# main_stack_dual_channel.net
KiCad netlist of a schematic drawn in Altium Designer
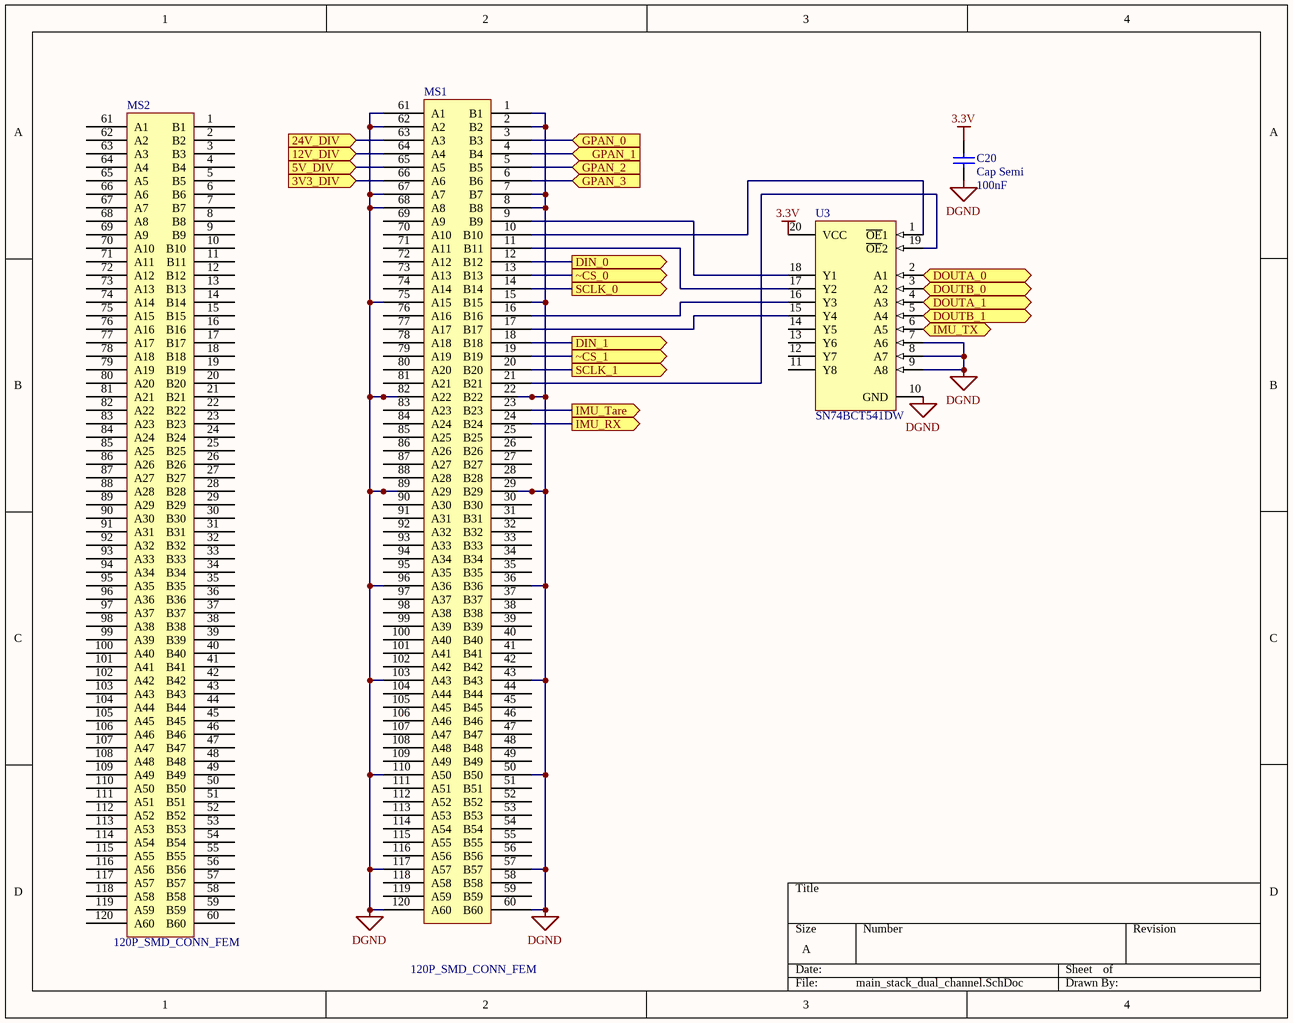
[diagram p0: main_stack_dual_channel.SchDoc]

(export (version "E")
  (design (tool "Eeschema 10.0.6"))
  (components
    (comp (ref "C20")
      (value "Cap Semi")
      (footprint "C0805")
      (description "Capacitor (Semiconductor SIM Model)")
      (fields (field (name "ALTIUM_VALUE") "100nF") (field (name "PUBLISHER") "Altium Limited"))
      (libsource (lib "Miscellaneous Devices") (part "Cap Semi"))
    )
    (comp (ref "MS1")
      (value "120P_SMD_CONN_FEM")
      (description "Main Stack Connector, Female")
      (fields (field (name "PART NUMBER") "FX2-120P-1.27SV(71)"))
      (libsource (lib "MDA_altium_common") (part "120P_SMD_CONN_FEM"))
    )
    (comp (ref "MS2")
      (value "120P_SMD_CONN_FEM")
      (description "Main Stack Connector, Female")
      (fields (field (name "PART NUMBER") "FX2-120P-1.27SV(71)"))
      (libsource (lib "MDA_altium_common") (part "120P_SMD_CONN_FEM"))
    )
    (comp (ref "U3")
      (value "SN74BCT541DW")
      (footprint "DW020_N")
      (description "Octal Buffer/Driver with 3-State Outputs")
      (fields (field (name "PUBLISHER") "Altium Limited"))
      (libsource (lib "TI Logic Buffer Line Driver") (part "SN74BCT541DW"))
    )
  )
  (nets
    (net (code "1") (name "/3V3_DIV") (class "Default")
      (node (ref "MS1") (pin "66") (pinfunction "A6_66") (pintype "passive"))
    )
    (net (code "2") (name "/5V_DIV") (class "Default")
      (node (ref "MS1") (pin "65") (pinfunction "A5_65") (pintype "passive"))
    )
    (net (code "3") (name "/12V_DIV") (class "Default")
      (node (ref "MS1") (pin "64") (pinfunction "A4_64") (pintype "passive"))
    )
    (net (code "4") (name "/24V_DIV") (class "Default")
      (node (ref "MS1") (pin "63") (pinfunction "A3_63") (pintype "passive"))
    )
    (net (code "5") (name "/DIN_0") (class "Default")
      (node (ref "MS1") (pin "12") (pinfunction "B12_12") (pintype "passive"))
    )
    (net (code "6") (name "/DIN_1") (class "Default")
      (node (ref "MS1") (pin "18") (pinfunction "B18_18") (pintype "passive"))
    )
    (net (code "7") (name "/DOUTA_0") (class "Default")
      (node (ref "U3") (pin "2") (pinfunction "A1_2") (pintype "input"))
    )
    (net (code "8") (name "/DOUTA_1") (class "Default")
      (node (ref "U3") (pin "4") (pinfunction "A3_4") (pintype "input"))
    )
    (net (code "9") (name "/DOUTB_0") (class "Default")
      (node (ref "U3") (pin "3") (pinfunction "A2_3") (pintype "input"))
    )
    (net (code "10") (name "/DOUTB_1") (class "Default")
      (node (ref "U3") (pin "5") (pinfunction "A4_5") (pintype "input"))
    )
    (net (code "11") (name "/GPAN_0") (class "Default")
      (node (ref "MS1") (pin "3") (pinfunction "B3_3") (pintype "passive"))
    )
    (net (code "12") (name "/GPAN_1") (class "Default")
      (node (ref "MS1") (pin "4") (pinfunction "B4_4") (pintype "passive"))
    )
    (net (code "13") (name "/GPAN_2") (class "Default")
      (node (ref "MS1") (pin "5") (pinfunction "B5_5") (pintype "passive"))
    )
    (net (code "14") (name "/GPAN_3") (class "Default")
      (node (ref "MS1") (pin "6") (pinfunction "B6_6") (pintype "passive"))
    )
    (net (code "15") (name "/IMU_RX") (class "Default")
      (node (ref "MS1") (pin "24") (pinfunction "B24_24") (pintype "passive"))
    )
    (net (code "16") (name "/IMU_TX") (class "Default")
      (node (ref "U3") (pin "6") (pinfunction "A5_6") (pintype "input"))
    )
    (net (code "17") (name "/IMU_Tare") (class "Default")
      (node (ref "MS1") (pin "23") (pinfunction "B23_23") (pintype "passive"))
    )
    (net (code "18") (name "/SCLK_0") (class "Default")
      (node (ref "MS1") (pin "14") (pinfunction "B14_14") (pintype "passive"))
    )
    (net (code "19") (name "/SCLK_1") (class "Default")
      (node (ref "MS1") (pin "20") (pinfunction "B20_20") (pintype "passive"))
    )
    (net (code "20") (name "/~CS_0") (class "Default")
      (node (ref "MS1") (pin "13") (pinfunction "B13_13") (pintype "passive"))
    )
    (net (code "21") (name "/~CS_1") (class "Default")
      (node (ref "MS1") (pin "19") (pinfunction "B19_19") (pintype "passive"))
    )
    (net (code "22") (name "3.3V") (class "Default")
      (node (ref "C20") (pin "2") (pinfunction "2_2") (pintype "passive"))
      (node (ref "U3") (pin "20") (pinfunction "VCC_20") (pintype "power_in"))
    )
    (net (code "23") (name "DGND") (class "Default")
      (node (ref "C20") (pin "1") (pinfunction "1_1") (pintype "passive"))
      (node (ref "MS1") (pin "1") (pinfunction "B1_1") (pintype "passive"))
      (node (ref "MS1") (pin "103") (pinfunction "A43_103") (pintype "passive"))
      (node (ref "MS1") (pin "110") (pinfunction "A50_110") (pintype "passive"))
      (node (ref "MS1") (pin "117") (pinfunction "A57_117") (pintype "passive"))
      (node (ref "MS1") (pin "120") (pinfunction "A60_120") (pintype "passive"))
      (node (ref "MS1") (pin "15") (pinfunction "B15_15") (pintype "passive"))
      (node (ref "MS1") (pin "2") (pinfunction "B2_2") (pintype "passive"))
      (node (ref "MS1") (pin "22") (pinfunction "B22_22") (pintype "passive"))
      (node (ref "MS1") (pin "29") (pinfunction "B29_29") (pintype "passive"))
      (node (ref "MS1") (pin "36") (pinfunction "B36_36") (pintype "passive"))
      (node (ref "MS1") (pin "43") (pinfunction "B43_43") (pintype "passive"))
      (node (ref "MS1") (pin "50") (pinfunction "B50_50") (pintype "passive"))
      (node (ref "MS1") (pin "57") (pinfunction "B57_57") (pintype "passive"))
      (node (ref "MS1") (pin "60") (pinfunction "B60_60") (pintype "passive"))
      (node (ref "MS1") (pin "61") (pinfunction "A1_61") (pintype "passive"))
      (node (ref "MS1") (pin "62") (pinfunction "A2_62") (pintype "passive"))
      (node (ref "MS1") (pin "67") (pinfunction "A7_67") (pintype "passive"))
      (node (ref "MS1") (pin "68") (pinfunction "A8_68") (pintype "passive"))
      (node (ref "MS1") (pin "7") (pinfunction "B7_7") (pintype "passive"))
      (node (ref "MS1") (pin "75") (pinfunction "A15_75") (pintype "passive"))
      (node (ref "MS1") (pin "8") (pinfunction "B8_8") (pintype "passive"))
      (node (ref "MS1") (pin "82") (pinfunction "A22_82") (pintype "passive"))
      (node (ref "MS1") (pin "89") (pinfunction "A29_89") (pintype "passive"))
      (node (ref "MS1") (pin "96") (pinfunction "A36_96") (pintype "passive"))
      (node (ref "U3") (pin "10") (pinfunction "GND_10") (pintype "power_in"))
      (node (ref "U3") (pin "7") (pinfunction "A6_7") (pintype "input"))
      (node (ref "U3") (pin "8") (pinfunction "A7_8") (pintype "input"))
      (node (ref "U3") (pin "9") (pinfunction "A8_9") (pintype "input"))
    )
    (net (code "24") (name "Net-(MS1-B9)") (class "Default")
      (node (ref "MS1") (pin "9") (pinfunction "B9_9") (pintype "passive"))
      (node (ref "U3") (pin "18") (pinfunction "Y1_18") (pintype "tri_state"))
    )
    (net (code "25") (name "Net-(MS1-B10)") (class "Default")
      (node (ref "MS1") (pin "10") (pinfunction "B10_10") (pintype "passive"))
      (node (ref "U3") (pin "1") (pinfunction "~{OE}1_1") (pintype "input"))
    )
    (net (code "26") (name "Net-(MS1-B11)") (class "Default")
      (node (ref "MS1") (pin "11") (pinfunction "B11_11") (pintype "passive"))
      (node (ref "U3") (pin "17") (pinfunction "Y2_17") (pintype "tri_state"))
    )
    (net (code "27") (name "Net-(MS1-B16)") (class "Default")
      (node (ref "MS1") (pin "16") (pinfunction "B16_16") (pintype "passive"))
      (node (ref "U3") (pin "16") (pinfunction "Y3_16") (pintype "tri_state"))
    )
    (net (code "28") (name "Net-(MS1-B17)") (class "Default")
      (node (ref "MS1") (pin "17") (pinfunction "B17_17") (pintype "passive"))
      (node (ref "U3") (pin "15") (pinfunction "Y4_15") (pintype "tri_state"))
    )
    (net (code "29") (name "Net-(MS1-B21)") (class "Default")
      (node (ref "MS1") (pin "21") (pinfunction "B21_21") (pintype "passive"))
      (node (ref "U3") (pin "19") (pinfunction "~{OE}2_19") (pintype "input"))
    )
    (net (code "30") (name "unconnected-(MS1-A9-Pad69)") (class "Default")
      (node (ref "MS1") (pin "69") (pinfunction "A9_69") (pintype "passive"))
    )
    (net (code "31") (name "unconnected-(MS1-A10-Pad70)") (class "Default")
      (node (ref "MS1") (pin "70") (pinfunction "A10_70") (pintype "passive"))
    )
    (net (code "32") (name "unconnected-(MS1-A11-Pad71)") (class "Default")
      (node (ref "MS1") (pin "71") (pinfunction "A11_71") (pintype "passive"))
    )
    (net (code "33") (name "unconnected-(MS1-A12-Pad72)") (class "Default")
      (node (ref "MS1") (pin "72") (pinfunction "A12_72") (pintype "passive"))
    )
    (net (code "34") (name "unconnected-(MS1-A13-Pad73)") (class "Default")
      (node (ref "MS1") (pin "73") (pinfunction "A13_73") (pintype "passive"))
    )
    (net (code "35") (name "unconnected-(MS1-A14-Pad74)") (class "Default")
      (node (ref "MS1") (pin "74") (pinfunction "A14_74") (pintype "passive"))
    )
    (net (code "36") (name "unconnected-(MS1-A16-Pad76)") (class "Default")
      (node (ref "MS1") (pin "76") (pinfunction "A16_76") (pintype "passive"))
    )
    (net (code "37") (name "unconnected-(MS1-A17-Pad77)") (class "Default")
      (node (ref "MS1") (pin "77") (pinfunction "A17_77") (pintype "passive"))
    )
    (net (code "38") (name "unconnected-(MS1-A18-Pad78)") (class "Default")
      (node (ref "MS1") (pin "78") (pinfunction "A18_78") (pintype "passive"))
    )
    (net (code "39") (name "unconnected-(MS1-A19-Pad79)") (class "Default")
      (node (ref "MS1") (pin "79") (pinfunction "A19_79") (pintype "passive"))
    )
    (net (code "40") (name "unconnected-(MS1-A20-Pad80)") (class "Default")
      (node (ref "MS1") (pin "80") (pinfunction "A20_80") (pintype "passive"))
    )
    (net (code "41") (name "unconnected-(MS1-A21-Pad81)") (class "Default")
      (node (ref "MS1") (pin "81") (pinfunction "A21_81") (pintype "passive"))
    )
    (net (code "42") (name "unconnected-(MS1-A23-Pad83)") (class "Default")
      (node (ref "MS1") (pin "83") (pinfunction "A23_83") (pintype "passive"))
    )
    (net (code "43") (name "unconnected-(MS1-A24-Pad84)") (class "Default")
      (node (ref "MS1") (pin "84") (pinfunction "A24_84") (pintype "passive"))
    )
    (net (code "44") (name "unconnected-(MS1-A25-Pad85)") (class "Default")
      (node (ref "MS1") (pin "85") (pinfunction "A25_85") (pintype "passive"))
    )
    (net (code "45") (name "unconnected-(MS1-A26-Pad86)") (class "Default")
      (node (ref "MS1") (pin "86") (pinfunction "A26_86") (pintype "passive"))
    )
    (net (code "46") (name "unconnected-(MS1-A27-Pad87)") (class "Default")
      (node (ref "MS1") (pin "87") (pinfunction "A27_87") (pintype "passive"))
    )
    (net (code "47") (name "unconnected-(MS1-A28-Pad88)") (class "Default")
      (node (ref "MS1") (pin "88") (pinfunction "A28_88") (pintype "passive"))
    )
    (net (code "48") (name "unconnected-(MS1-A30-Pad90)") (class "Default")
      (node (ref "MS1") (pin "90") (pinfunction "A30_90") (pintype "passive"))
    )
    (net (code "49") (name "unconnected-(MS1-A31-Pad91)") (class "Default")
      (node (ref "MS1") (pin "91") (pinfunction "A31_91") (pintype "passive"))
    )
    (net (code "50") (name "unconnected-(MS1-A32-Pad92)") (class "Default")
      (node (ref "MS1") (pin "92") (pinfunction "A32_92") (pintype "passive"))
    )
    (net (code "51") (name "unconnected-(MS1-A33-Pad93)") (class "Default")
      (node (ref "MS1") (pin "93") (pinfunction "A33_93") (pintype "passive"))
    )
    (net (code "52") (name "unconnected-(MS1-A34-Pad94)") (class "Default")
      (node (ref "MS1") (pin "94") (pinfunction "A34_94") (pintype "passive"))
    )
    (net (code "53") (name "unconnected-(MS1-A35-Pad95)") (class "Default")
      (node (ref "MS1") (pin "95") (pinfunction "A35_95") (pintype "passive"))
    )
    (net (code "54") (name "unconnected-(MS1-A37-Pad97)") (class "Default")
      (node (ref "MS1") (pin "97") (pinfunction "A37_97") (pintype "passive"))
    )
    (net (code "55") (name "unconnected-(MS1-A38-Pad98)") (class "Default")
      (node (ref "MS1") (pin "98") (pinfunction "A38_98") (pintype "passive"))
    )
    (net (code "56") (name "unconnected-(MS1-A39-Pad99)") (class "Default")
      (node (ref "MS1") (pin "99") (pinfunction "A39_99") (pintype "passive"))
    )
    (net (code "57") (name "unconnected-(MS1-A40-Pad100)") (class "Default")
      (node (ref "MS1") (pin "100") (pinfunction "A40_100") (pintype "passive"))
    )
    (net (code "58") (name "unconnected-(MS1-A41-Pad101)") (class "Default")
      (node (ref "MS1") (pin "101") (pinfunction "A41_101") (pintype "passive"))
    )
    (net (code "59") (name "unconnected-(MS1-A42-Pad102)") (class "Default")
      (node (ref "MS1") (pin "102") (pinfunction "A42_102") (pintype "passive"))
    )
    (net (code "60") (name "unconnected-(MS1-A44-Pad104)") (class "Default")
      (node (ref "MS1") (pin "104") (pinfunction "A44_104") (pintype "passive"))
    )
    (net (code "61") (name "unconnected-(MS1-A45-Pad105)") (class "Default")
      (node (ref "MS1") (pin "105") (pinfunction "A45_105") (pintype "passive"))
    )
    (net (code "62") (name "unconnected-(MS1-A46-Pad106)") (class "Default")
      (node (ref "MS1") (pin "106") (pinfunction "A46_106") (pintype "passive"))
    )
    (net (code "63") (name "unconnected-(MS1-A47-Pad107)") (class "Default")
      (node (ref "MS1") (pin "107") (pinfunction "A47_107") (pintype "passive"))
    )
    (net (code "64") (name "unconnected-(MS1-A48-Pad108)") (class "Default")
      (node (ref "MS1") (pin "108") (pinfunction "A48_108") (pintype "passive"))
    )
    (net (code "65") (name "unconnected-(MS1-A49-Pad109)") (class "Default")
      (node (ref "MS1") (pin "109") (pinfunction "A49_109") (pintype "passive"))
    )
    (net (code "66") (name "unconnected-(MS1-A51-Pad111)") (class "Default")
      (node (ref "MS1") (pin "111") (pinfunction "A51_111") (pintype "passive"))
    )
    (net (code "67") (name "unconnected-(MS1-A52-Pad112)") (class "Default")
      (node (ref "MS1") (pin "112") (pinfunction "A52_112") (pintype "passive"))
    )
    (net (code "68") (name "unconnected-(MS1-A53-Pad113)") (class "Default")
      (node (ref "MS1") (pin "113") (pinfunction "A53_113") (pintype "passive"))
    )
    (net (code "69") (name "unconnected-(MS1-A54-Pad114)") (class "Default")
      (node (ref "MS1") (pin "114") (pinfunction "A54_114") (pintype "passive"))
    )
    (net (code "70") (name "unconnected-(MS1-A55-Pad115)") (class "Default")
      (node (ref "MS1") (pin "115") (pinfunction "A55_115") (pintype "passive"))
    )
    (net (code "71") (name "unconnected-(MS1-A56-Pad116)") (class "Default")
      (node (ref "MS1") (pin "116") (pinfunction "A56_116") (pintype "passive"))
    )
    (net (code "72") (name "unconnected-(MS1-A58-Pad118)") (class "Default")
      (node (ref "MS1") (pin "118") (pinfunction "A58_118") (pintype "passive"))
    )
    (net (code "73") (name "unconnected-(MS1-A59-Pad119)") (class "Default")
      (node (ref "MS1") (pin "119") (pinfunction "A59_119") (pintype "passive"))
    )
    (net (code "74") (name "unconnected-(MS1-B25-Pad25)") (class "Default")
      (node (ref "MS1") (pin "25") (pinfunction "B25_25") (pintype "passive"))
    )
    (net (code "75") (name "unconnected-(MS1-B26-Pad26)") (class "Default")
      (node (ref "MS1") (pin "26") (pinfunction "B26_26") (pintype "passive"))
    )
    (net (code "76") (name "unconnected-(MS1-B27-Pad27)") (class "Default")
      (node (ref "MS1") (pin "27") (pinfunction "B27_27") (pintype "passive"))
    )
    (net (code "77") (name "unconnected-(MS1-B28-Pad28)") (class "Default")
      (node (ref "MS1") (pin "28") (pinfunction "B28_28") (pintype "passive"))
    )
    (net (code "78") (name "unconnected-(MS1-B30-Pad30)") (class "Default")
      (node (ref "MS1") (pin "30") (pinfunction "B30_30") (pintype "passive"))
    )
    (net (code "79") (name "unconnected-(MS1-B31-Pad31)") (class "Default")
      (node (ref "MS1") (pin "31") (pinfunction "B31_31") (pintype "passive"))
    )
    (net (code "80") (name "unconnected-(MS1-B32-Pad32)") (class "Default")
      (node (ref "MS1") (pin "32") (pinfunction "B32_32") (pintype "passive"))
    )
    (net (code "81") (name "unconnected-(MS1-B33-Pad33)") (class "Default")
      (node (ref "MS1") (pin "33") (pinfunction "B33_33") (pintype "passive"))
    )
    (net (code "82") (name "unconnected-(MS1-B34-Pad34)") (class "Default")
      (node (ref "MS1") (pin "34") (pinfunction "B34_34") (pintype "passive"))
    )
    (net (code "83") (name "unconnected-(MS1-B35-Pad35)") (class "Default")
      (node (ref "MS1") (pin "35") (pinfunction "B35_35") (pintype "passive"))
    )
    (net (code "84") (name "unconnected-(MS1-B37-Pad37)") (class "Default")
      (node (ref "MS1") (pin "37") (pinfunction "B37_37") (pintype "passive"))
    )
    (net (code "85") (name "unconnected-(MS1-B38-Pad38)") (class "Default")
      (node (ref "MS1") (pin "38") (pinfunction "B38_38") (pintype "passive"))
    )
    (net (code "86") (name "unconnected-(MS1-B39-Pad39)") (class "Default")
      (node (ref "MS1") (pin "39") (pinfunction "B39_39") (pintype "passive"))
    )
    (net (code "87") (name "unconnected-(MS1-B40-Pad40)") (class "Default")
      (node (ref "MS1") (pin "40") (pinfunction "B40_40") (pintype "passive"))
    )
    (net (code "88") (name "unconnected-(MS1-B41-Pad41)") (class "Default")
      (node (ref "MS1") (pin "41") (pinfunction "B41_41") (pintype "passive"))
    )
    (net (code "89") (name "unconnected-(MS1-B42-Pad42)") (class "Default")
      (node (ref "MS1") (pin "42") (pinfunction "B42_42") (pintype "passive"))
    )
    (net (code "90") (name "unconnected-(MS1-B44-Pad44)") (class "Default")
      (node (ref "MS1") (pin "44") (pinfunction "B44_44") (pintype "passive"))
    )
    (net (code "91") (name "unconnected-(MS1-B45-Pad45)") (class "Default")
      (node (ref "MS1") (pin "45") (pinfunction "B45_45") (pintype "passive"))
    )
    (net (code "92") (name "unconnected-(MS1-B46-Pad46)") (class "Default")
      (node (ref "MS1") (pin "46") (pinfunction "B46_46") (pintype "passive"))
    )
    (net (code "93") (name "unconnected-(MS1-B47-Pad47)") (class "Default")
      (node (ref "MS1") (pin "47") (pinfunction "B47_47") (pintype "passive"))
    )
    (net (code "94") (name "unconnected-(MS1-B48-Pad48)") (class "Default")
      (node (ref "MS1") (pin "48") (pinfunction "B48_48") (pintype "passive"))
    )
    (net (code "95") (name "unconnected-(MS1-B49-Pad49)") (class "Default")
      (node (ref "MS1") (pin "49") (pinfunction "B49_49") (pintype "passive"))
    )
    (net (code "96") (name "unconnected-(MS1-B51-Pad51)") (class "Default")
      (node (ref "MS1") (pin "51") (pinfunction "B51_51") (pintype "passive"))
    )
    (net (code "97") (name "unconnected-(MS1-B52-Pad52)") (class "Default")
      (node (ref "MS1") (pin "52") (pinfunction "B52_52") (pintype "passive"))
    )
    (net (code "98") (name "unconnected-(MS1-B53-Pad53)") (class "Default")
      (node (ref "MS1") (pin "53") (pinfunction "B53_53") (pintype "passive"))
    )
    (net (code "99") (name "unconnected-(MS1-B54-Pad54)") (class "Default")
      (node (ref "MS1") (pin "54") (pinfunction "B54_54") (pintype "passive"))
    )
    (net (code "100") (name "unconnected-(MS1-B55-Pad55)") (class "Default")
      (node (ref "MS1") (pin "55") (pinfunction "B55_55") (pintype "passive"))
    )
    (net (code "101") (name "unconnected-(MS1-B56-Pad56)") (class "Default")
      (node (ref "MS1") (pin "56") (pinfunction "B56_56") (pintype "passive"))
    )
    (net (code "102") (name "unconnected-(MS1-B58-Pad58)") (class "Default")
      (node (ref "MS1") (pin "58") (pinfunction "B58_58") (pintype "passive"))
    )
    (net (code "103") (name "unconnected-(MS1-B59-Pad59)") (class "Default")
      (node (ref "MS1") (pin "59") (pinfunction "B59_59") (pintype "passive"))
    )
    (net (code "104") (name "unconnected-(MS2-A1-Pad61)") (class "Default")
      (node (ref "MS2") (pin "61") (pinfunction "A1_61") (pintype "passive"))
    )
    (net (code "105") (name "unconnected-(MS2-A2-Pad62)") (class "Default")
      (node (ref "MS2") (pin "62") (pinfunction "A2_62") (pintype "passive"))
    )
    (net (code "106") (name "unconnected-(MS2-A3-Pad63)") (class "Default")
      (node (ref "MS2") (pin "63") (pinfunction "A3_63") (pintype "passive"))
    )
    (net (code "107") (name "unconnected-(MS2-A4-Pad64)") (class "Default")
      (node (ref "MS2") (pin "64") (pinfunction "A4_64") (pintype "passive"))
    )
    (net (code "108") (name "unconnected-(MS2-A5-Pad65)") (class "Default")
      (node (ref "MS2") (pin "65") (pinfunction "A5_65") (pintype "passive"))
    )
    (net (code "109") (name "unconnected-(MS2-A6-Pad66)") (class "Default")
      (node (ref "MS2") (pin "66") (pinfunction "A6_66") (pintype "passive"))
    )
    (net (code "110") (name "unconnected-(MS2-A7-Pad67)") (class "Default")
      (node (ref "MS2") (pin "67") (pinfunction "A7_67") (pintype "passive"))
    )
    (net (code "111") (name "unconnected-(MS2-A8-Pad68)") (class "Default")
      (node (ref "MS2") (pin "68") (pinfunction "A8_68") (pintype "passive"))
    )
    (net (code "112") (name "unconnected-(MS2-A9-Pad69)") (class "Default")
      (node (ref "MS2") (pin "69") (pinfunction "A9_69") (pintype "passive"))
    )
    (net (code "113") (name "unconnected-(MS2-A10-Pad70)") (class "Default")
      (node (ref "MS2") (pin "70") (pinfunction "A10_70") (pintype "passive"))
    )
    (net (code "114") (name "unconnected-(MS2-A11-Pad71)") (class "Default")
      (node (ref "MS2") (pin "71") (pinfunction "A11_71") (pintype "passive"))
    )
    (net (code "115") (name "unconnected-(MS2-A12-Pad72)") (class "Default")
      (node (ref "MS2") (pin "72") (pinfunction "A12_72") (pintype "passive"))
    )
    (net (code "116") (name "unconnected-(MS2-A13-Pad73)") (class "Default")
      (node (ref "MS2") (pin "73") (pinfunction "A13_73") (pintype "passive"))
    )
    (net (code "117") (name "unconnected-(MS2-A14-Pad74)") (class "Default")
      (node (ref "MS2") (pin "74") (pinfunction "A14_74") (pintype "passive"))
    )
    (net (code "118") (name "unconnected-(MS2-A15-Pad75)") (class "Default")
      (node (ref "MS2") (pin "75") (pinfunction "A15_75") (pintype "passive"))
    )
    (net (code "119") (name "unconnected-(MS2-A16-Pad76)") (class "Default")
      (node (ref "MS2") (pin "76") (pinfunction "A16_76") (pintype "passive"))
    )
    (net (code "120") (name "unconnected-(MS2-A17-Pad77)") (class "Default")
      (node (ref "MS2") (pin "77") (pinfunction "A17_77") (pintype "passive"))
    )
    (net (code "121") (name "unconnected-(MS2-A18-Pad78)") (class "Default")
      (node (ref "MS2") (pin "78") (pinfunction "A18_78") (pintype "passive"))
    )
    (net (code "122") (name "unconnected-(MS2-A19-Pad79)") (class "Default")
      (node (ref "MS2") (pin "79") (pinfunction "A19_79") (pintype "passive"))
    )
    (net (code "123") (name "unconnected-(MS2-A20-Pad80)") (class "Default")
      (node (ref "MS2") (pin "80") (pinfunction "A20_80") (pintype "passive"))
    )
    (net (code "124") (name "unconnected-(MS2-A21-Pad81)") (class "Default")
      (node (ref "MS2") (pin "81") (pinfunction "A21_81") (pintype "passive"))
    )
    (net (code "125") (name "unconnected-(MS2-A22-Pad82)") (class "Default")
      (node (ref "MS2") (pin "82") (pinfunction "A22_82") (pintype "passive"))
    )
    (net (code "126") (name "unconnected-(MS2-A23-Pad83)") (class "Default")
      (node (ref "MS2") (pin "83") (pinfunction "A23_83") (pintype "passive"))
    )
    (net (code "127") (name "unconnected-(MS2-A24-Pad84)") (class "Default")
      (node (ref "MS2") (pin "84") (pinfunction "A24_84") (pintype "passive"))
    )
    (net (code "128") (name "unconnected-(MS2-A25-Pad85)") (class "Default")
      (node (ref "MS2") (pin "85") (pinfunction "A25_85") (pintype "passive"))
    )
    (net (code "129") (name "unconnected-(MS2-A26-Pad86)") (class "Default")
      (node (ref "MS2") (pin "86") (pinfunction "A26_86") (pintype "passive"))
    )
    (net (code "130") (name "unconnected-(MS2-A27-Pad87)") (class "Default")
      (node (ref "MS2") (pin "87") (pinfunction "A27_87") (pintype "passive"))
    )
    (net (code "131") (name "unconnected-(MS2-A28-Pad88)") (class "Default")
      (node (ref "MS2") (pin "88") (pinfunction "A28_88") (pintype "passive"))
    )
    (net (code "132") (name "unconnected-(MS2-A29-Pad89)") (class "Default")
      (node (ref "MS2") (pin "89") (pinfunction "A29_89") (pintype "passive"))
    )
    (net (code "133") (name "unconnected-(MS2-A30-Pad90)") (class "Default")
      (node (ref "MS2") (pin "90") (pinfunction "A30_90") (pintype "passive"))
    )
    (net (code "134") (name "unconnected-(MS2-A31-Pad91)") (class "Default")
      (node (ref "MS2") (pin "91") (pinfunction "A31_91") (pintype "passive"))
    )
    (net (code "135") (name "unconnected-(MS2-A32-Pad92)") (class "Default")
      (node (ref "MS2") (pin "92") (pinfunction "A32_92") (pintype "passive"))
    )
    (net (code "136") (name "unconnected-(MS2-A33-Pad93)") (class "Default")
      (node (ref "MS2") (pin "93") (pinfunction "A33_93") (pintype "passive"))
    )
    (net (code "137") (name "unconnected-(MS2-A34-Pad94)") (class "Default")
      (node (ref "MS2") (pin "94") (pinfunction "A34_94") (pintype "passive"))
    )
    (net (code "138") (name "unconnected-(MS2-A35-Pad95)") (class "Default")
      (node (ref "MS2") (pin "95") (pinfunction "A35_95") (pintype "passive"))
    )
    (net (code "139") (name "unconnected-(MS2-A36-Pad96)") (class "Default")
      (node (ref "MS2") (pin "96") (pinfunction "A36_96") (pintype "passive"))
    )
    (net (code "140") (name "unconnected-(MS2-A37-Pad97)") (class "Default")
      (node (ref "MS2") (pin "97") (pinfunction "A37_97") (pintype "passive"))
    )
    (net (code "141") (name "unconnected-(MS2-A38-Pad98)") (class "Default")
      (node (ref "MS2") (pin "98") (pinfunction "A38_98") (pintype "passive"))
    )
    (net (code "142") (name "unconnected-(MS2-A39-Pad99)") (class "Default")
      (node (ref "MS2") (pin "99") (pinfunction "A39_99") (pintype "passive"))
    )
    (net (code "143") (name "unconnected-(MS2-A40-Pad100)") (class "Default")
      (node (ref "MS2") (pin "100") (pinfunction "A40_100") (pintype "passive"))
    )
    (net (code "144") (name "unconnected-(MS2-A41-Pad101)") (class "Default")
      (node (ref "MS2") (pin "101") (pinfunction "A41_101") (pintype "passive"))
    )
    (net (code "145") (name "unconnected-(MS2-A42-Pad102)") (class "Default")
      (node (ref "MS2") (pin "102") (pinfunction "A42_102") (pintype "passive"))
    )
    (net (code "146") (name "unconnected-(MS2-A43-Pad103)") (class "Default")
      (node (ref "MS2") (pin "103") (pinfunction "A43_103") (pintype "passive"))
    )
    (net (code "147") (name "unconnected-(MS2-A44-Pad104)") (class "Default")
      (node (ref "MS2") (pin "104") (pinfunction "A44_104") (pintype "passive"))
    )
    (net (code "148") (name "unconnected-(MS2-A45-Pad105)") (class "Default")
      (node (ref "MS2") (pin "105") (pinfunction "A45_105") (pintype "passive"))
    )
    (net (code "149") (name "unconnected-(MS2-A46-Pad106)") (class "Default")
      (node (ref "MS2") (pin "106") (pinfunction "A46_106") (pintype "passive"))
    )
    (net (code "150") (name "unconnected-(MS2-A47-Pad107)") (class "Default")
      (node (ref "MS2") (pin "107") (pinfunction "A47_107") (pintype "passive"))
    )
    (net (code "151") (name "unconnected-(MS2-A48-Pad108)") (class "Default")
      (node (ref "MS2") (pin "108") (pinfunction "A48_108") (pintype "passive"))
    )
    (net (code "152") (name "unconnected-(MS2-A49-Pad109)") (class "Default")
      (node (ref "MS2") (pin "109") (pinfunction "A49_109") (pintype "passive"))
    )
    (net (code "153") (name "unconnected-(MS2-A50-Pad110)") (class "Default")
      (node (ref "MS2") (pin "110") (pinfunction "A50_110") (pintype "passive"))
    )
    (net (code "154") (name "unconnected-(MS2-A51-Pad111)") (class "Default")
      (node (ref "MS2") (pin "111") (pinfunction "A51_111") (pintype "passive"))
    )
    (net (code "155") (name "unconnected-(MS2-A52-Pad112)") (class "Default")
      (node (ref "MS2") (pin "112") (pinfunction "A52_112") (pintype "passive"))
    )
    (net (code "156") (name "unconnected-(MS2-A53-Pad113)") (class "Default")
      (node (ref "MS2") (pin "113") (pinfunction "A53_113") (pintype "passive"))
    )
    (net (code "157") (name "unconnected-(MS2-A54-Pad114)") (class "Default")
      (node (ref "MS2") (pin "114") (pinfunction "A54_114") (pintype "passive"))
    )
    (net (code "158") (name "unconnected-(MS2-A55-Pad115)") (class "Default")
      (node (ref "MS2") (pin "115") (pinfunction "A55_115") (pintype "passive"))
    )
    (net (code "159") (name "unconnected-(MS2-A56-Pad116)") (class "Default")
      (node (ref "MS2") (pin "116") (pinfunction "A56_116") (pintype "passive"))
    )
    (net (code "160") (name "unconnected-(MS2-A57-Pad117)") (class "Default")
      (node (ref "MS2") (pin "117") (pinfunction "A57_117") (pintype "passive"))
    )
    (net (code "161") (name "unconnected-(MS2-A58-Pad118)") (class "Default")
      (node (ref "MS2") (pin "118") (pinfunction "A58_118") (pintype "passive"))
    )
    (net (code "162") (name "unconnected-(MS2-A59-Pad119)") (class "Default")
      (node (ref "MS2") (pin "119") (pinfunction "A59_119") (pintype "passive"))
    )
    (net (code "163") (name "unconnected-(MS2-A60-Pad120)") (class "Default")
      (node (ref "MS2") (pin "120") (pinfunction "A60_120") (pintype "passive"))
    )
    (net (code "164") (name "unconnected-(MS2-B1-Pad1)") (class "Default")
      (node (ref "MS2") (pin "1") (pinfunction "B1_1") (pintype "passive"))
    )
    (net (code "165") (name "unconnected-(MS2-B2-Pad2)") (class "Default")
      (node (ref "MS2") (pin "2") (pinfunction "B2_2") (pintype "passive"))
    )
    (net (code "166") (name "unconnected-(MS2-B3-Pad3)") (class "Default")
      (node (ref "MS2") (pin "3") (pinfunction "B3_3") (pintype "passive"))
    )
    (net (code "167") (name "unconnected-(MS2-B4-Pad4)") (class "Default")
      (node (ref "MS2") (pin "4") (pinfunction "B4_4") (pintype "passive"))
    )
    (net (code "168") (name "unconnected-(MS2-B5-Pad5)") (class "Default")
      (node (ref "MS2") (pin "5") (pinfunction "B5_5") (pintype "passive"))
    )
    (net (code "169") (name "unconnected-(MS2-B6-Pad6)") (class "Default")
      (node (ref "MS2") (pin "6") (pinfunction "B6_6") (pintype "passive"))
    )
    (net (code "170") (name "unconnected-(MS2-B7-Pad7)") (class "Default")
      (node (ref "MS2") (pin "7") (pinfunction "B7_7") (pintype "passive"))
    )
    (net (code "171") (name "unconnected-(MS2-B8-Pad8)") (class "Default")
      (node (ref "MS2") (pin "8") (pinfunction "B8_8") (pintype "passive"))
    )
    (net (code "172") (name "unconnected-(MS2-B9-Pad9)") (class "Default")
      (node (ref "MS2") (pin "9") (pinfunction "B9_9") (pintype "passive"))
    )
    (net (code "173") (name "unconnected-(MS2-B10-Pad10)") (class "Default")
      (node (ref "MS2") (pin "10") (pinfunction "B10_10") (pintype "passive"))
    )
    (net (code "174") (name "unconnected-(MS2-B11-Pad11)") (class "Default")
      (node (ref "MS2") (pin "11") (pinfunction "B11_11") (pintype "passive"))
    )
    (net (code "175") (name "unconnected-(MS2-B12-Pad12)") (class "Default")
      (node (ref "MS2") (pin "12") (pinfunction "B12_12") (pintype "passive"))
    )
    (net (code "176") (name "unconnected-(MS2-B13-Pad13)") (class "Default")
      (node (ref "MS2") (pin "13") (pinfunction "B13_13") (pintype "passive"))
    )
    (net (code "177") (name "unconnected-(MS2-B14-Pad14)") (class "Default")
      (node (ref "MS2") (pin "14") (pinfunction "B14_14") (pintype "passive"))
    )
    (net (code "178") (name "unconnected-(MS2-B15-Pad15)") (class "Default")
      (node (ref "MS2") (pin "15") (pinfunction "B15_15") (pintype "passive"))
    )
    (net (code "179") (name "unconnected-(MS2-B16-Pad16)") (class "Default")
      (node (ref "MS2") (pin "16") (pinfunction "B16_16") (pintype "passive"))
    )
    (net (code "180") (name "unconnected-(MS2-B17-Pad17)") (class "Default")
      (node (ref "MS2") (pin "17") (pinfunction "B17_17") (pintype "passive"))
    )
    (net (code "181") (name "unconnected-(MS2-B18-Pad18)") (class "Default")
      (node (ref "MS2") (pin "18") (pinfunction "B18_18") (pintype "passive"))
    )
    (net (code "182") (name "unconnected-(MS2-B19-Pad19)") (class "Default")
      (node (ref "MS2") (pin "19") (pinfunction "B19_19") (pintype "passive"))
    )
    (net (code "183") (name "unconnected-(MS2-B20-Pad20)") (class "Default")
      (node (ref "MS2") (pin "20") (pinfunction "B20_20") (pintype "passive"))
    )
    (net (code "184") (name "unconnected-(MS2-B21-Pad21)") (class "Default")
      (node (ref "MS2") (pin "21") (pinfunction "B21_21") (pintype "passive"))
    )
    (net (code "185") (name "unconnected-(MS2-B22-Pad22)") (class "Default")
      (node (ref "MS2") (pin "22") (pinfunction "B22_22") (pintype "passive"))
    )
    (net (code "186") (name "unconnected-(MS2-B23-Pad23)") (class "Default")
      (node (ref "MS2") (pin "23") (pinfunction "B23_23") (pintype "passive"))
    )
    (net (code "187") (name "unconnected-(MS2-B24-Pad24)") (class "Default")
      (node (ref "MS2") (pin "24") (pinfunction "B24_24") (pintype "passive"))
    )
    (net (code "188") (name "unconnected-(MS2-B25-Pad25)") (class "Default")
      (node (ref "MS2") (pin "25") (pinfunction "B25_25") (pintype "passive"))
    )
    (net (code "189") (name "unconnected-(MS2-B26-Pad26)") (class "Default")
      (node (ref "MS2") (pin "26") (pinfunction "B26_26") (pintype "passive"))
    )
    (net (code "190") (name "unconnected-(MS2-B27-Pad27)") (class "Default")
      (node (ref "MS2") (pin "27") (pinfunction "B27_27") (pintype "passive"))
    )
    (net (code "191") (name "unconnected-(MS2-B28-Pad28)") (class "Default")
      (node (ref "MS2") (pin "28") (pinfunction "B28_28") (pintype "passive"))
    )
    (net (code "192") (name "unconnected-(MS2-B29-Pad29)") (class "Default")
      (node (ref "MS2") (pin "29") (pinfunction "B29_29") (pintype "passive"))
    )
    (net (code "193") (name "unconnected-(MS2-B30-Pad30)") (class "Default")
      (node (ref "MS2") (pin "30") (pinfunction "B30_30") (pintype "passive"))
    )
    (net (code "194") (name "unconnected-(MS2-B31-Pad31)") (class "Default")
      (node (ref "MS2") (pin "31") (pinfunction "B31_31") (pintype "passive"))
    )
    (net (code "195") (name "unconnected-(MS2-B32-Pad32)") (class "Default")
      (node (ref "MS2") (pin "32") (pinfunction "B32_32") (pintype "passive"))
    )
    (net (code "196") (name "unconnected-(MS2-B33-Pad33)") (class "Default")
      (node (ref "MS2") (pin "33") (pinfunction "B33_33") (pintype "passive"))
    )
    (net (code "197") (name "unconnected-(MS2-B34-Pad34)") (class "Default")
      (node (ref "MS2") (pin "34") (pinfunction "B34_34") (pintype "passive"))
    )
    (net (code "198") (name "unconnected-(MS2-B35-Pad35)") (class "Default")
      (node (ref "MS2") (pin "35") (pinfunction "B35_35") (pintype "passive"))
    )
    (net (code "199") (name "unconnected-(MS2-B36-Pad36)") (class "Default")
      (node (ref "MS2") (pin "36") (pinfunction "B36_36") (pintype "passive"))
    )
    (net (code "200") (name "unconnected-(MS2-B37-Pad37)") (class "Default")
      (node (ref "MS2") (pin "37") (pinfunction "B37_37") (pintype "passive"))
    )
    (net (code "201") (name "unconnected-(MS2-B38-Pad38)") (class "Default")
      (node (ref "MS2") (pin "38") (pinfunction "B38_38") (pintype "passive"))
    )
    (net (code "202") (name "unconnected-(MS2-B39-Pad39)") (class "Default")
      (node (ref "MS2") (pin "39") (pinfunction "B39_39") (pintype "passive"))
    )
    (net (code "203") (name "unconnected-(MS2-B40-Pad40)") (class "Default")
      (node (ref "MS2") (pin "40") (pinfunction "B40_40") (pintype "passive"))
    )
    (net (code "204") (name "unconnected-(MS2-B41-Pad41)") (class "Default")
      (node (ref "MS2") (pin "41") (pinfunction "B41_41") (pintype "passive"))
    )
    (net (code "205") (name "unconnected-(MS2-B42-Pad42)") (class "Default")
      (node (ref "MS2") (pin "42") (pinfunction "B42_42") (pintype "passive"))
    )
    (net (code "206") (name "unconnected-(MS2-B43-Pad43)") (class "Default")
      (node (ref "MS2") (pin "43") (pinfunction "B43_43") (pintype "passive"))
    )
    (net (code "207") (name "unconnected-(MS2-B44-Pad44)") (class "Default")
      (node (ref "MS2") (pin "44") (pinfunction "B44_44") (pintype "passive"))
    )
    (net (code "208") (name "unconnected-(MS2-B45-Pad45)") (class "Default")
      (node (ref "MS2") (pin "45") (pinfunction "B45_45") (pintype "passive"))
    )
    (net (code "209") (name "unconnected-(MS2-B46-Pad46)") (class "Default")
      (node (ref "MS2") (pin "46") (pinfunction "B46_46") (pintype "passive"))
    )
    (net (code "210") (name "unconnected-(MS2-B47-Pad47)") (class "Default")
      (node (ref "MS2") (pin "47") (pinfunction "B47_47") (pintype "passive"))
    )
    (net (code "211") (name "unconnected-(MS2-B48-Pad48)") (class "Default")
      (node (ref "MS2") (pin "48") (pinfunction "B48_48") (pintype "passive"))
    )
    (net (code "212") (name "unconnected-(MS2-B49-Pad49)") (class "Default")
      (node (ref "MS2") (pin "49") (pinfunction "B49_49") (pintype "passive"))
    )
    (net (code "213") (name "unconnected-(MS2-B50-Pad50)") (class "Default")
      (node (ref "MS2") (pin "50") (pinfunction "B50_50") (pintype "passive"))
    )
    (net (code "214") (name "unconnected-(MS2-B51-Pad51)") (class "Default")
      (node (ref "MS2") (pin "51") (pinfunction "B51_51") (pintype "passive"))
    )
    (net (code "215") (name "unconnected-(MS2-B52-Pad52)") (class "Default")
      (node (ref "MS2") (pin "52") (pinfunction "B52_52") (pintype "passive"))
    )
    (net (code "216") (name "unconnected-(MS2-B53-Pad53)") (class "Default")
      (node (ref "MS2") (pin "53") (pinfunction "B53_53") (pintype "passive"))
    )
    (net (code "217") (name "unconnected-(MS2-B54-Pad54)") (class "Default")
      (node (ref "MS2") (pin "54") (pinfunction "B54_54") (pintype "passive"))
    )
    (net (code "218") (name "unconnected-(MS2-B55-Pad55)") (class "Default")
      (node (ref "MS2") (pin "55") (pinfunction "B55_55") (pintype "passive"))
    )
    (net (code "219") (name "unconnected-(MS2-B56-Pad56)") (class "Default")
      (node (ref "MS2") (pin "56") (pinfunction "B56_56") (pintype "passive"))
    )
    (net (code "220") (name "unconnected-(MS2-B57-Pad57)") (class "Default")
      (node (ref "MS2") (pin "57") (pinfunction "B57_57") (pintype "passive"))
    )
    (net (code "221") (name "unconnected-(MS2-B58-Pad58)") (class "Default")
      (node (ref "MS2") (pin "58") (pinfunction "B58_58") (pintype "passive"))
    )
    (net (code "222") (name "unconnected-(MS2-B59-Pad59)") (class "Default")
      (node (ref "MS2") (pin "59") (pinfunction "B59_59") (pintype "passive"))
    )
    (net (code "223") (name "unconnected-(MS2-B60-Pad60)") (class "Default")
      (node (ref "MS2") (pin "60") (pinfunction "B60_60") (pintype "passive"))
    )
    (net (code "224") (name "unconnected-(U3-Y5-Pad14)") (class "Default")
      (node (ref "U3") (pin "14") (pinfunction "Y5_14") (pintype "tri_state"))
    )
    (net (code "225") (name "unconnected-(U3-Y6-Pad13)") (class "Default")
      (node (ref "U3") (pin "13") (pinfunction "Y6_13") (pintype "tri_state"))
    )
    (net (code "226") (name "unconnected-(U3-Y7-Pad12)") (class "Default")
      (node (ref "U3") (pin "12") (pinfunction "Y7_12") (pintype "tri_state"))
    )
    (net (code "227") (name "unconnected-(U3-Y8-Pad11)") (class "Default")
      (node (ref "U3") (pin "11") (pinfunction "Y8_11") (pintype "tri_state"))
    )
  )
)
